# assistPower.net
KiCad netlist of a schematic drawn in Altium Designer
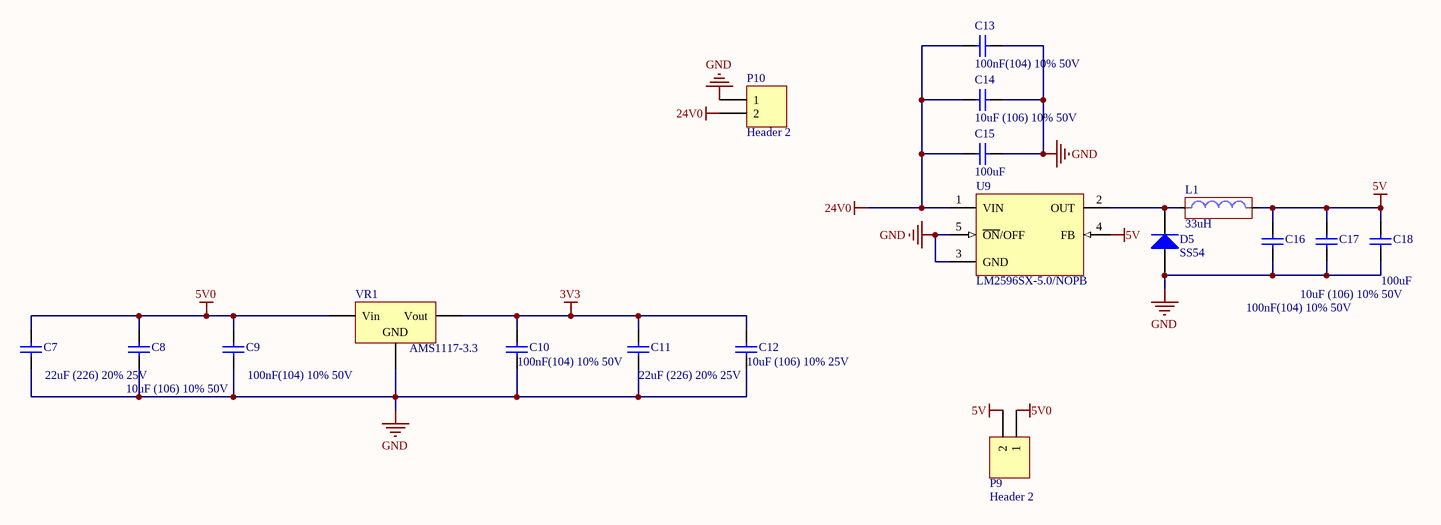
[diagram p0: assistPower.SchDoc]

(export (version "E")
  (design (tool "Eeschema 10.0.6"))
  (components
    (comp (ref "C7")
      (value "22uF (226) 20% 25V")
      (footprint "0805_C")
      (description "贴片电容")
      (libsource (lib "Miscellaneous Devices LC") (part "0805 22uF (226) 20% 25V"))
    )
    (comp (ref "C8")
      (value "10uF (106) 10% 50V")
      (footprint "1206_C")
      (description "贴片电容")
      (libsource (lib "Miscellaneous Devices LC") (part "1206 10uF (106) 10% 50V"))
    )
    (comp (ref "C9")
      (value "100nF(104) 10% 50V")
      (footprint "0805_C")
      (description "贴片电容")
      (libsource (lib "Miscellaneous Devices LC") (part "0805 100nF(104) 10% 50V"))
    )
    (comp (ref "C10")
      (value "100nF(104) 10% 50V")
      (footprint "0805_C")
      (description "贴片电容")
      (libsource (lib "Miscellaneous Devices LC") (part "0805 100nF(104) 10% 50V"))
    )
    (comp (ref "C11")
      (value "22uF (226) 20% 25V")
      (footprint "0805_C")
      (description "贴片电容")
      (libsource (lib "Miscellaneous Devices LC") (part "0805 22uF (226) 20% 25V"))
    )
    (comp (ref "C12")
      (value "10uF (106) 10% 25V")
      (footprint "0805_C")
      (description "贴片电容")
      (libsource (lib "Miscellaneous Devices LC") (part "0805 10uF (106) 10% 25V"))
    )
    (comp (ref "C13")
      (value "100nF(104) 10% 50V")
      (footprint "0805_C")
      (description "贴片电容")
      (libsource (lib "Miscellaneous Devices LC") (part "0805 100nF(104) 10% 50V"))
    )
    (comp (ref "C14")
      (value "10uF (106) 10% 50V")
      (footprint "1206_C")
      (description "贴片电容")
      (libsource (lib "Miscellaneous Devices LC") (part "1206 10uF (106) 10% 50V"))
    )
    (comp (ref "C15")
      (value "100uF")
      (footprint "C100uF")
      (description "贴片电容")
      (fields (field (name "Comment") "Cap") (field (name "PUBLISHER") "Altium Limited"))
      (libsource (lib "Sparks") (part "Cap"))
    )
    (comp (ref "C16")
      (value "100nF(104) 10% 50V")
      (footprint "0805_C")
      (description "贴片电容")
      (libsource (lib "Miscellaneous Devices LC") (part "0805 100nF(104) 10% 50V"))
    )
    (comp (ref "C17")
      (value "10uF (106) 10% 50V")
      (footprint "1206_C")
      (description "贴片电容")
      (libsource (lib "Miscellaneous Devices LC") (part "1206 10uF (106) 10% 50V"))
    )
    (comp (ref "C18")
      (value "100uF")
      (footprint "C100uF")
      (description "贴片电容")
      (fields (field (name "Comment") "Cap") (field (name "PUBLISHER") "Altium Limited"))
      (libsource (lib "Sparks") (part "Cap"))
    )
    (comp (ref "D5")
      (value "SS54")
      (footprint "SMA(DO-214AC)_S1")
      (description "二极管")
      (libsource (lib "Miscellaneous Devices LC") (part "SMA(DO-214AC) SS54"))
    )
    (comp (ref "L1")
      (value "33uH")
      (footprint "L-SMD-7")
      (description "Inductor")
      (libsource (lib "Landzo") (part "Inductor"))
    )
    (comp (ref "P9")
      (value "Header 2")
      (footprint "HDR1X2")
      (description "Header, 2-Pin")
      (fields (field (name "PUBLISHER") "Altium Limited"))
      (libsource (lib "") (part "Header 2_1"))
    )
    (comp (ref "P10")
      (value "Header 2")
      (footprint "5.08-2P")
      (description "Header, 2-Pin")
      (fields (field (name "PUBLISHER") "Altium Limited"))
      (libsource (lib "Sparks") (part "Header 2"))
    )
    (comp (ref "U9")
      (value "LM2596SX-5.0/NOPB")
      (footprint "TO-263-5")
      (description "DC-DC芯片")
      (libsource (lib "Miscellaneous Devices LC") (part "LM2596SX-5.0/NOPB_[C10002]"))
    )
    (comp (ref "VR1")
      (value "AMS1117-3.3")
      (footprint "SOT-223")
      (description "低压差线性稳压(LDO)")
      (libsource (lib "Miscellaneous Devices LC") (part "SOT-223 AMS1117-3.3"))
    )
  )
  (nets
    (net (code "1") (name "3V3") (class "Default")
      (node (ref "C10") (pin "2") (pinfunction "2_2") (pintype "passive"))
      (node (ref "C11") (pin "2") (pinfunction "2_2") (pintype "passive"))
      (node (ref "C12") (pin "2") (pinfunction "2_2") (pintype "passive"))
      (node (ref "VR1") (pin "2") (pinfunction "Vout_2") (pintype "passive"))
    )
    (net (code "2") (name "5V") (class "Default")
      (node (ref "C16") (pin "2") (pinfunction "2_2") (pintype "passive"))
      (node (ref "C17") (pin "2") (pinfunction "2_2") (pintype "passive"))
      (node (ref "C18") (pin "1") (pinfunction "1_1") (pintype "passive"))
      (node (ref "L1") (pin "1") (pinfunction "1_1") (pintype "passive"))
      (node (ref "P9") (pin "2") (pinfunction "2_2") (pintype "passive"))
      (node (ref "U9") (pin "4") (pinfunction "FB_4") (pintype "input"))
    )
    (net (code "3") (name "5V0") (class "Default")
      (node (ref "C7") (pin "2") (pinfunction "2_2") (pintype "passive"))
      (node (ref "C8") (pin "2") (pinfunction "2_2") (pintype "passive"))
      (node (ref "C9") (pin "2") (pinfunction "2_2") (pintype "passive"))
      (node (ref "P9") (pin "1") (pinfunction "1_1") (pintype "passive"))
      (node (ref "VR1") (pin "3") (pinfunction "Vin_3") (pintype "passive"))
    )
    (net (code "4") (name "24V0") (class "Default")
      (node (ref "C13") (pin "1") (pinfunction "1_1") (pintype "passive"))
      (node (ref "C14") (pin "1") (pinfunction "1_1") (pintype "passive"))
      (node (ref "C15") (pin "2") (pinfunction "2_2") (pintype "passive"))
      (node (ref "P10") (pin "2") (pinfunction "2_2") (pintype "passive"))
      (node (ref "U9") (pin "1") (pinfunction "VIN_1") (pintype "power_in"))
    )
    (net (code "5") (name "GND") (class "Default")
      (node (ref "C10") (pin "1") (pinfunction "1_1") (pintype "passive"))
      (node (ref "C11") (pin "1") (pinfunction "1_1") (pintype "passive"))
      (node (ref "C12") (pin "1") (pinfunction "1_1") (pintype "passive"))
      (node (ref "C13") (pin "2") (pinfunction "2_2") (pintype "passive"))
      (node (ref "C14") (pin "2") (pinfunction "2_2") (pintype "passive"))
      (node (ref "C15") (pin "1") (pinfunction "1_1") (pintype "passive"))
      (node (ref "C16") (pin "1") (pinfunction "1_1") (pintype "passive"))
      (node (ref "C17") (pin "1") (pinfunction "1_1") (pintype "passive"))
      (node (ref "C18") (pin "2") (pinfunction "2_2") (pintype "passive"))
      (node (ref "C7") (pin "1") (pinfunction "1_1") (pintype "passive"))
      (node (ref "C8") (pin "1") (pinfunction "1_1") (pintype "passive"))
      (node (ref "C9") (pin "1") (pinfunction "1_1") (pintype "passive"))
      (node (ref "D5") (pin "1") (pinfunction "A_1") (pintype "passive"))
      (node (ref "P10") (pin "1") (pinfunction "1_1") (pintype "passive"))
      (node (ref "U9") (pin "3") (pinfunction "GND_3") (pintype "power_in"))
      (node (ref "U9") (pin "5") (pinfunction "~{ON}/OFF_5") (pintype "input"))
      (node (ref "VR1") (pin "1") (pinfunction "GND_1") (pintype "passive"))
    )
    (net (code "6") (name "Net-(D5-K)") (class "Default")
      (node (ref "D5") (pin "2") (pinfunction "K_2") (pintype "passive"))
      (node (ref "L1") (pin "2") (pinfunction "2_2") (pintype "passive"))
      (node (ref "U9") (pin "2") (pinfunction "OUT_2") (pintype "power_in"))
    )
  )
)
